# PCB_Arduino_r3.net
KiCad netlist of a schematic drawn in EAGLE
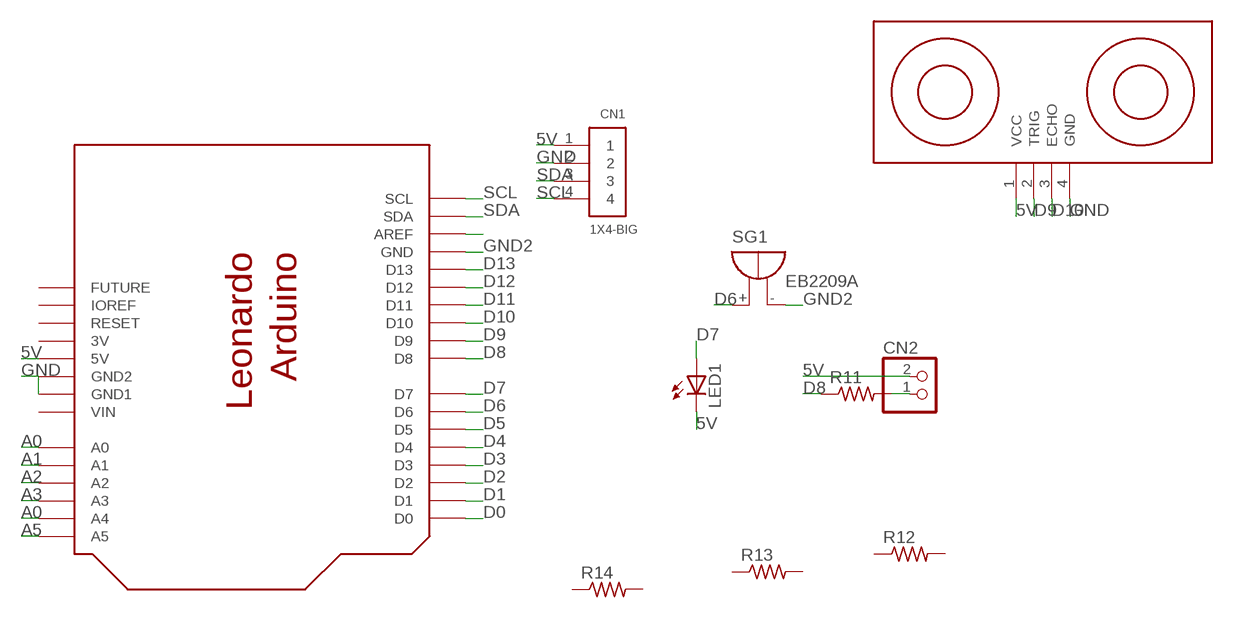
[diagram p0: schematic, sheet 1]

(export (version "E")
  (design (tool "Eeschema 10.0.6"))
  (components
    (comp (ref "CN1")
      (value "1X4-BIG")
      (footprint "eagle-import:1X04-BIG")
      (libsource (lib "eagle-import") (part "1X4-BIG"))
    )
    (comp (ref "CN2")
      (value "JST_2PIN-THM")
      (footprint "eagle-import:JST-PH-2-THM")
      (libsource (lib "eagle-import") (part "JST_2PIN-THM"))
    )
    (comp (ref "LED1")
      (value "LEDB152")
      (footprint "eagle-import:Q62902-B152")
      (libsource (lib "eagle-import") (part "LEDB152"))
    )
    (comp (ref "R11")
      (value "R-US_0204/7")
      (footprint "eagle-import:0204_7")
      (libsource (lib "eagle-import") (part "R-US_0204/7"))
    )
    (comp (ref "R12")
      (value "R-US_0204/7")
      (footprint "eagle-import:0204_7")
      (libsource (lib "eagle-import") (part "R-US_0204/7"))
    )
    (comp (ref "R13")
      (value "R-US_0204/7")
      (footprint "eagle-import:0204_7")
      (libsource (lib "eagle-import") (part "R-US_0204/7"))
    )
    (comp (ref "R14")
      (value "R-US_0204/7")
      (footprint "eagle-import:0204_7")
      (libsource (lib "eagle-import") (part "R-US_0204/7"))
    )
    (comp (ref "SG1")
      (value "EB2209A")
      (footprint "eagle-import:EB2209A")
      (libsource (lib "eagle-import") (part "EB2209A"))
    )
    (comp (ref "U$1")
      (value "ARDUINO_LEONARDO")
      (footprint "eagle-import:ARDUINO_LEONARDO")
      (libsource (lib "eagle-import") (part "ARDUINO_LEONARDO"))
    )
    (comp (ref "U$2")
      (value "ULTRASONIC-HC-SR04")
      (footprint "eagle-import:ULTRASONIC-HC-SR04")
      (libsource (lib "eagle-import") (part "ULTRASONIC-HC-SR04"))
    )
  )
  (nets
    (net (code "1") (name "/3V") (class "Default")
      (node (ref "U$1") (pin "3V") (pinfunction "3V_3V") (pintype "power_in"))
    )
    (net (code "2") (name "/5V") (class "Default")
      (node (ref "CN1") (pin "1") (pinfunction "1_1") (pintype "bidirectional"))
      (node (ref "CN2") (pin "2") (pinfunction "1_2") (pintype "passive"))
      (node (ref "LED1") (pin "K") (pinfunction "C_K") (pintype "passive"))
      (node (ref "U$1") (pin "5V") (pinfunction "5V_5V") (pintype "power_in"))
      (node (ref "U$2") (pin "1") (pinfunction "VCC_1") (pintype "power_in"))
    )
    (net (code "3") (name "/A0") (class "Default")
      (node (ref "U$1") (pin "A0") (pinfunction "A0_A0") (pintype "bidirectional"))
    )
    (net (code "4") (name "/A1") (class "Default")
      (node (ref "U$1") (pin "A1") (pinfunction "A1_A1") (pintype "bidirectional"))
    )
    (net (code "5") (name "/A2") (class "Default")
      (node (ref "U$1") (pin "A2") (pinfunction "A2_A2") (pintype "bidirectional"))
    )
    (net (code "6") (name "/A3") (class "Default")
      (node (ref "U$1") (pin "A3") (pinfunction "A3_A3") (pintype "bidirectional"))
    )
    (net (code "7") (name "/A5") (class "Default")
      (node (ref "U$1") (pin "A5") (pinfunction "A5_A5") (pintype "bidirectional"))
    )
    (net (code "8") (name "/D0") (class "Default")
      (node (ref "U$1") (pin "D0") (pinfunction "D0_D0") (pintype "bidirectional"))
    )
    (net (code "9") (name "/D1") (class "Default")
      (node (ref "U$1") (pin "D1") (pinfunction "D1_D1") (pintype "bidirectional"))
    )
    (net (code "10") (name "/D2") (class "Default")
      (node (ref "U$1") (pin "D2") (pinfunction "D2_D2") (pintype "bidirectional"))
    )
    (net (code "11") (name "/D3") (class "Default")
      (node (ref "U$1") (pin "D3") (pinfunction "D3_D3") (pintype "bidirectional"))
    )
    (net (code "12") (name "/D4") (class "Default")
      (node (ref "U$1") (pin "D4") (pinfunction "D4_D4") (pintype "bidirectional"))
    )
    (net (code "13") (name "/D5") (class "Default")
      (node (ref "U$1") (pin "D5") (pinfunction "D5_D5") (pintype "bidirectional"))
    )
    (net (code "14") (name "/D6") (class "Default")
      (node (ref "SG1") (pin "+") (pinfunction "+_+") (pintype "passive"))
      (node (ref "U$1") (pin "D6") (pinfunction "D6_D6") (pintype "bidirectional"))
    )
    (net (code "15") (name "/D7") (class "Default")
      (node (ref "LED1") (pin "A") (pinfunction "A_A") (pintype "passive"))
      (node (ref "U$1") (pin "D7") (pinfunction "D7_D7") (pintype "bidirectional"))
    )
    (net (code "16") (name "/D8") (class "Default")
      (node (ref "R11") (pin "1") (pinfunction "1_1") (pintype "passive"))
      (node (ref "U$1") (pin "D8") (pinfunction "D8_D8") (pintype "bidirectional"))
    )
    (net (code "17") (name "/D9") (class "Default")
      (node (ref "U$1") (pin "D9") (pinfunction "D9_D9") (pintype "bidirectional"))
      (node (ref "U$2") (pin "2") (pinfunction "TRIG_2") (pintype "input"))
    )
    (net (code "18") (name "/D10") (class "Default")
      (node (ref "U$1") (pin "D10") (pinfunction "D10_D10") (pintype "bidirectional"))
      (node (ref "U$2") (pin "3") (pinfunction "ECHO_3") (pintype "output"))
    )
    (net (code "19") (name "/D11") (class "Default")
      (node (ref "U$1") (pin "D11") (pinfunction "D11_D11") (pintype "bidirectional"))
    )
    (net (code "20") (name "/D12") (class "Default")
      (node (ref "U$1") (pin "D12") (pinfunction "D12_D12") (pintype "bidirectional"))
    )
    (net (code "21") (name "/D13") (class "Default")
      (node (ref "U$1") (pin "D13") (pinfunction "D13_D13") (pintype "bidirectional"))
    )
    (net (code "22") (name "/GND") (class "Default")
      (node (ref "CN1") (pin "2") (pinfunction "2_2") (pintype "bidirectional"))
      (node (ref "U$1") (pin "GND$2") (pinfunction "GND2_GND$2") (pintype "power_in"))
      (node (ref "U$1") (pin "GND$3") (pinfunction "GND1_GND$3") (pintype "power_in"))
      (node (ref "U$2") (pin "4") (pinfunction "GND_4") (pintype "power_in"))
    )
    (net (code "23") (name "/GND2") (class "Default")
      (node (ref "SG1") (pin "-") (pinfunction "-_-") (pintype "passive"))
      (node (ref "U$1") (pin "GND") (pinfunction "GND_GND") (pintype "power_in"))
    )
    (net (code "24") (name "/SCL") (class "Default")
      (node (ref "CN1") (pin "4") (pinfunction "4_4") (pintype "bidirectional"))
      (node (ref "U$1") (pin "SCL") (pinfunction "SCL_SCL") (pintype "bidirectional"))
    )
    (net (code "25") (name "/SDA") (class "Default")
      (node (ref "CN1") (pin "3") (pinfunction "3_3") (pintype "bidirectional"))
      (node (ref "U$1") (pin "SDA") (pinfunction "SDA_SDA") (pintype "bidirectional"))
    )
    (net (code "26") (name "/VIN") (class "Default")
      (node (ref "U$1") (pin "VIN") (pinfunction "VIN_VIN") (pintype "power_in"))
    )
    (net (code "27") (name "Net-(CN2-2)") (class "Default")
      (node (ref "CN2") (pin "1") (pinfunction "2_1") (pintype "passive"))
      (node (ref "R11") (pin "2") (pinfunction "2_2") (pintype "passive"))
    )
    (net (code "28") (name "unconnected-(R12-Pad1)") (class "Default")
      (node (ref "R12") (pin "1") (pinfunction "1_1") (pintype "passive"))
    )
    (net (code "29") (name "unconnected-(R12-Pad2)") (class "Default")
      (node (ref "R12") (pin "2") (pinfunction "2_2") (pintype "passive"))
    )
    (net (code "30") (name "unconnected-(R13-Pad1)") (class "Default")
      (node (ref "R13") (pin "1") (pinfunction "1_1") (pintype "passive"))
    )
    (net (code "31") (name "unconnected-(R13-Pad2)") (class "Default")
      (node (ref "R13") (pin "2") (pinfunction "2_2") (pintype "passive"))
    )
    (net (code "32") (name "unconnected-(R14-Pad1)") (class "Default")
      (node (ref "R14") (pin "1") (pinfunction "1_1") (pintype "passive"))
    )
    (net (code "33") (name "unconnected-(R14-Pad2)") (class "Default")
      (node (ref "R14") (pin "2") (pinfunction "2_2") (pintype "passive"))
    )
    (net (code "34") (name "unconnected-(U$1-FUTURE-PadRESERVED)") (class "Default")
      (node (ref "U$1") (pin "RESERVED") (pinfunction "FUTURE_RESERVED") (pintype "bidirectional"))
    )
    (net (code "35") (name "unconnected-(U$1-PadA4)") (class "Default")
      (node (ref "U$1") (pin "A4") (pinfunction "A4_A4") (pintype "bidirectional"))
    )
    (net (code "36") (name "unconnected-(U$1-PadAREF)") (class "Default")
      (node (ref "U$1") (pin "AREF") (pinfunction "AREF_AREF") (pintype "bidirectional"))
    )
    (net (code "37") (name "unconnected-(U$1-PadIOREF)") (class "Default")
      (node (ref "U$1") (pin "IOREF") (pinfunction "IOREF_IOREF") (pintype "bidirectional"))
    )
    (net (code "38") (name "unconnected-(U$1-PadRESET)") (class "Default")
      (node (ref "U$1") (pin "RESET") (pinfunction "RESET_RESET") (pintype "bidirectional"))
    )
  )
)
